# Voeding.net
KiCad netlist of a schematic drawn in Altium Designer
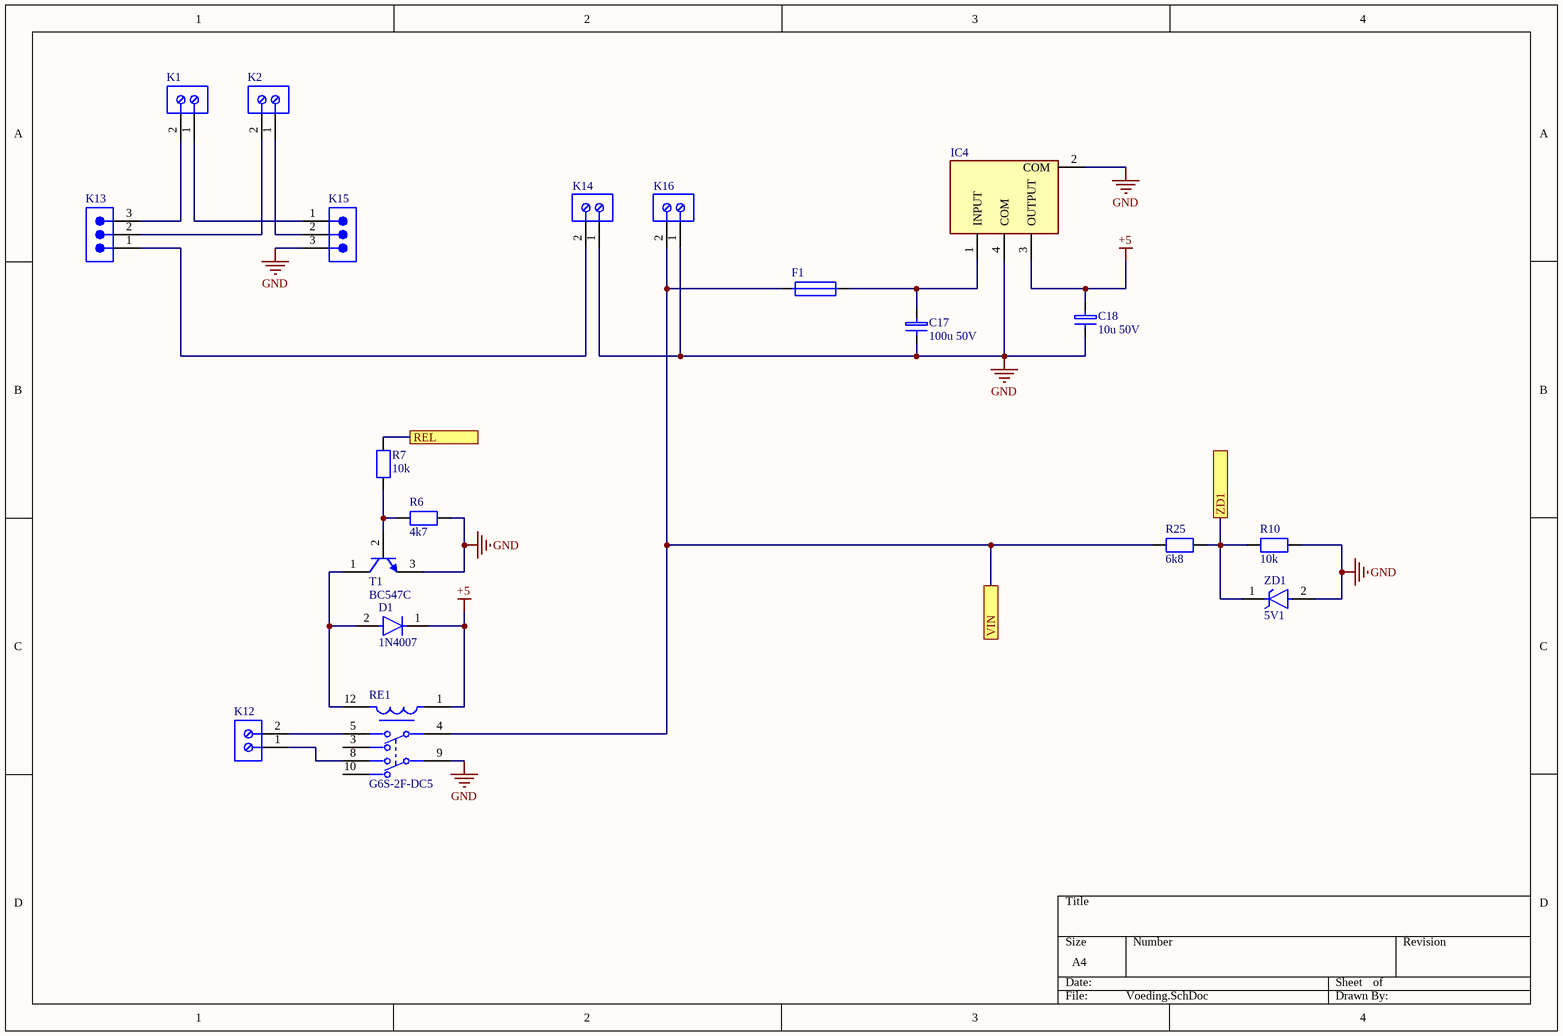
[diagram p0: Voeding.SchDoc]

(export (version "E")
  (design (tool "Eeschema 10.0.6"))
  (components
    (comp (ref "C17")
      (value "100u 50V")
      (footprint "CAPACITOR100UF")
      (description "860010683032 WCAP-ATG8 Aluminum Electrolytic Capacitors")
      (fields (field (name "TOLERANCE") "20%"))
      (libsource (lib "Soldeerstation Schematic") (part "CapacitorPol"))
    )
    (comp (ref "C18")
      (value "10u 50V")
      (footprint "CAPACITOR100UF")
      (description "860010683032 WCAP-ATG8 Aluminum Electrolytic Capacitors")
      (fields (field (name "TOLERANCE") "20%"))
      (libsource (lib "Soldeerstation Schematic") (part "CapacitorPol"))
    )
    (comp (ref "D1")
      (value "1N4007")
      (footprint "1N4007")
      (description "DIODE GEN PURP 1KV 1A DO41")
      (libsource (lib "Soldeerstation Schematic") (part "Diode"))
    )
    (comp (ref "F1")
      (value "696101000002")
      (footprint "FuseHolder")
      (libsource (lib "Soldeerstation Schematic") (part "FuseHolder"))
    )
    (comp (ref "IC4")
      (value "TL780-05CKTTR")
      (footprint "DC-DC Convertor")
      (description "IC REG LIN 5V 1.5A DDPAK/TO263-3")
      (libsource (lib "Soldeerstation Schematic") (part "DC/DC Convertor"))
    )
    (comp (ref "K1")
      (value "~")
      (footprint "Shroefconnecter")
      (description "Female Header, Pitch 5 mm, 1 x 2 Position, Height 10 mm, Tail Length 3.5 mm, Rohs, Bulk")
      (fields (field (name "VOLTAGE") "300V") (field (name "MANUFACTURER") "TE Connectivity"))
      (libsource (lib "Soldeerstation Schematic") (part "Schroefconnector"))
    )
    (comp (ref "K2")
      (value "~")
      (footprint "Shroefconnecter")
      (description "Female Header, Pitch 5 mm, 1 x 2 Position, Height 10 mm, Tail Length 3.5 mm, Rohs, Bulk")
      (fields (field (name "VOLTAGE") "300V") (field (name "MANUFACTURER") "TE Connectivity"))
      (libsource (lib "Soldeerstation Schematic") (part "Schroefconnector"))
    )
    (comp (ref "K12")
      (value "282836-2")
      (footprint "Shroefconnecter")
      (description "Female Header, Pitch 5 mm, 1 x 2 Position, Height 10 mm, Tail Length 3.5 mm, Rohs, Bulk")
      (fields (field (name "VOLTAGE") "300V") (field (name "MANUFACTURER") "TE Connectivity"))
      (libsource (lib "Soldeerstation Schematic") (part "Schroefconnector"))
    )
    (comp (ref "K13")
      (value "~")
      (footprint "[3][1]Pinheader")
      (libsource (lib "Soldeerstation Schematic") (part "[3][1]Pinheader"))
    )
    (comp (ref "K14")
      (value "282836-2")
      (footprint "Shroefconnecter")
      (description "Female Header, Pitch 5 mm, 1 x 2 Position, Height 10 mm, Tail Length 3.5 mm, Rohs, Bulk")
      (fields (field (name "VOLTAGE") "300V") (field (name "MANUFACTURER") "TE Connectivity"))
      (libsource (lib "Soldeerstation Schematic") (part "Schroefconnector"))
    )
    (comp (ref "K15")
      (value "61300311121")
      (footprint "[3][1]Pinheader")
      (libsource (lib "Soldeerstation Schematic") (part "[3][1]Pinheader"))
    )
    (comp (ref "K16")
      (value "282836-2")
      (footprint "Shroefconnecter")
      (description "Female Header, Pitch 5 mm, 1 x 2 Position, Height 10 mm, Tail Length 3.5 mm, Rohs, Bulk")
      (fields (field (name "VOLTAGE") "300V") (field (name "MANUFACTURER") "TE Connectivity"))
      (libsource (lib "Soldeerstation Schematic") (part "Schroefconnector"))
    )
    (comp (ref "R6")
      (value "4k7")
      (footprint "Resistor")
      (fields (field (name "MANUFACTURER") "Vishay Dale") (field (name "PART NUMBER") "CRCW08050000Z0EA"))
      (libsource (lib "Soldeerstation Schematic") (part "Resistor"))
    )
    (comp (ref "R7")
      (value "10k")
      (footprint "Resistor")
      (fields (field (name "MANUFACTURER") "Vishay Dale") (field (name "PART NUMBER") "CRCW08050000Z0EA"))
      (libsource (lib "Soldeerstation Schematic") (part "Resistor"))
    )
    (comp (ref "R10")
      (value "10k")
      (footprint "Resistor")
      (fields (field (name "MANUFACTURER") "Vishay Dale") (field (name "PART NUMBER") "CRCW08050000Z0EA"))
      (libsource (lib "Soldeerstation Schematic") (part "Resistor"))
    )
    (comp (ref "R25")
      (value "6k8")
      (footprint "Resistor")
      (fields (field (name "MANUFACTURER") "Vishay Dale") (field (name "PART NUMBER") "CRCW08050000Z0EA"))
      (libsource (lib "Soldeerstation Schematic") (part "Resistor"))
    )
    (comp (ref "RE1")
      (value "G6S-2F-DC5")
      (footprint "VermogenRelais")
      (description "RELAY TELECOM DPDT 2A 5VDC")
      (fields
        (field (name "MANUFACTURER") "Omron")
        (field (name "OCTOPART") "https://octopart.com/g6s-2f-dc5-omron-85236")
      )
      (libsource (lib "Soldeerstation Schematic") (part "VermogenRelais"))
    )
    (comp (ref "T1")
      (value "BC547C")
      (footprint "BC547C")
      (description "Amplifier Transistor, NPN Silicon, 3-Pin TO-92, Bulk Box")
      (fields (field (name "MANUFACTURER") "On Semiconductor"))
      (libsource (lib "Soldeerstation Schematic") (part "BC547C"))
    )
    (comp (ref "ZD1")
      (value "5V1")
      (footprint "Zenerdiode")
      (description "Zener Voltage Regulator, 500 mW, 2-Pin SOD-123, Pb-Free, Tape and Reel")
      (fields (field (name "PARTNUMBER") "MMSZ4689T1G") (field (name "MANUFACTURER") "On Semiconductor"))
      (libsource (lib "Soldeerstation Schematic") (part "Zenerdiode"))
    )
  )
  (nets
    (net (code "1") (name "+5") (class "Default")
      (node (ref "C18") (pin "1") (pinfunction "1_1") (pintype "passive"))
      (node (ref "D1") (pin "1") (pinfunction "C_1") (pintype "passive"))
      (node (ref "IC4") (pin "3") (pinfunction "OUTPUT_3") (pintype "power_in"))
      (node (ref "RE1") (pin "1") (pinfunction "1_1") (pintype "passive"))
    )
    (net (code "2") (name "/REL") (class "Default")
      (node (ref "R7") (pin "1") (pinfunction "1_1") (pintype "passive"))
    )
    (net (code "3") (name "/VIN") (class "Default")
      (node (ref "F1") (pin "1") (pinfunction "1_1") (pintype "passive"))
      (node (ref "K16") (pin "2") (pinfunction "2_2") (pintype "passive"))
      (node (ref "R25") (pin "1") (pinfunction "1_1") (pintype "passive"))
      (node (ref "RE1") (pin "4") (pinfunction "4_4") (pintype "passive"))
    )
    (net (code "4") (name "/ZD1") (class "Default")
      (node (ref "R10") (pin "1") (pinfunction "1_1") (pintype "passive"))
      (node (ref "R25") (pin "2") (pinfunction "2_2") (pintype "passive"))
      (node (ref "ZD1") (pin "1") (pinfunction "K_1") (pintype "passive"))
    )
    (net (code "5") (name "GND") (class "Default")
      (node (ref "C17") (pin "2") (pinfunction "2_2") (pintype "passive"))
      (node (ref "C18") (pin "2") (pinfunction "2_2") (pintype "passive"))
      (node (ref "IC4") (pin "2") (pinfunction "COM_2") (pintype "passive"))
      (node (ref "IC4") (pin "4") (pinfunction "COM_4") (pintype "passive"))
      (node (ref "K14") (pin "1") (pinfunction "1_1") (pintype "passive"))
      (node (ref "K15") (pin "3") (pinfunction "3_3") (pintype "passive"))
      (node (ref "K16") (pin "1") (pinfunction "1_1") (pintype "passive"))
      (node (ref "R10") (pin "2") (pinfunction "2_2") (pintype "passive"))
      (node (ref "R6") (pin "2") (pinfunction "2_2") (pintype "passive"))
      (node (ref "RE1") (pin "9") (pinfunction "9_9") (pintype "passive"))
      (node (ref "T1") (pin "3") (pinfunction "E_3") (pintype "passive"))
      (node (ref "ZD1") (pin "2") (pinfunction "A_2") (pintype "passive"))
    )
    (net (code "6") (name "Net-(D1-A)") (class "Default")
      (node (ref "D1") (pin "2") (pinfunction "A_2") (pintype "passive"))
      (node (ref "RE1") (pin "12") (pinfunction "12_12") (pintype "passive"))
      (node (ref "T1") (pin "1") (pinfunction "C_1") (pintype "passive"))
    )
    (net (code "7") (name "Net-(IC4-INPUT)") (class "Default")
      (node (ref "C17") (pin "1") (pinfunction "1_1") (pintype "passive"))
      (node (ref "F1") (pin "2") (pinfunction "2_2") (pintype "passive"))
      (node (ref "IC4") (pin "1") (pinfunction "INPUT_1") (pintype "power_in"))
    )
    (net (code "8") (name "Net-(K1-Pad1)") (class "Default")
      (node (ref "K1") (pin "1") (pinfunction "1_1") (pintype "passive"))
      (node (ref "K15") (pin "1") (pinfunction "1_1") (pintype "passive"))
    )
    (net (code "9") (name "Net-(K1-Pad2)") (class "Default")
      (node (ref "K1") (pin "2") (pinfunction "2_2") (pintype "passive"))
      (node (ref "K13") (pin "3") (pinfunction "3_3") (pintype "passive"))
    )
    (net (code "10") (name "Net-(K12-Pad1)") (class "Default")
      (node (ref "K12") (pin "1") (pinfunction "1_1") (pintype "passive"))
      (node (ref "RE1") (pin "8") (pinfunction "8_8") (pintype "passive"))
    )
    (net (code "11") (name "Net-(K12-Pad2)") (class "Default")
      (node (ref "K12") (pin "2") (pinfunction "2_2") (pintype "passive"))
      (node (ref "RE1") (pin "5") (pinfunction "5_5") (pintype "passive"))
    )
    (net (code "12") (name "Net-(K13-Pad1)") (class "Default")
      (node (ref "K13") (pin "1") (pinfunction "1_1") (pintype "passive"))
      (node (ref "K14") (pin "2") (pinfunction "2_2") (pintype "passive"))
    )
    (net (code "13") (name "Net-(K13-Pad2)") (class "Default")
      (node (ref "K13") (pin "2") (pinfunction "2_2") (pintype "passive"))
      (node (ref "K2") (pin "2") (pinfunction "2_2") (pintype "passive"))
    )
    (net (code "14") (name "Net-(K15-Pad2)") (class "Default")
      (node (ref "K15") (pin "2") (pinfunction "2_2") (pintype "passive"))
      (node (ref "K2") (pin "1") (pinfunction "1_1") (pintype "passive"))
    )
    (net (code "15") (name "Net-(T1-B)") (class "Default")
      (node (ref "R6") (pin "1") (pinfunction "1_1") (pintype "passive"))
      (node (ref "R7") (pin "2") (pinfunction "2_2") (pintype "passive"))
      (node (ref "T1") (pin "2") (pinfunction "B_2") (pintype "passive"))
    )
    (net (code "16") (name "unconnected-(RE1-Pad3)") (class "Default")
      (node (ref "RE1") (pin "3") (pinfunction "3_3") (pintype "passive"))
    )
    (net (code "17") (name "unconnected-(RE1-Pad10)") (class "Default")
      (node (ref "RE1") (pin "10") (pinfunction "10_10") (pintype "passive"))
    )
  )
)
